# atWork_Remote.net
KiCad netlist of a schematic drawn in Altium Designer
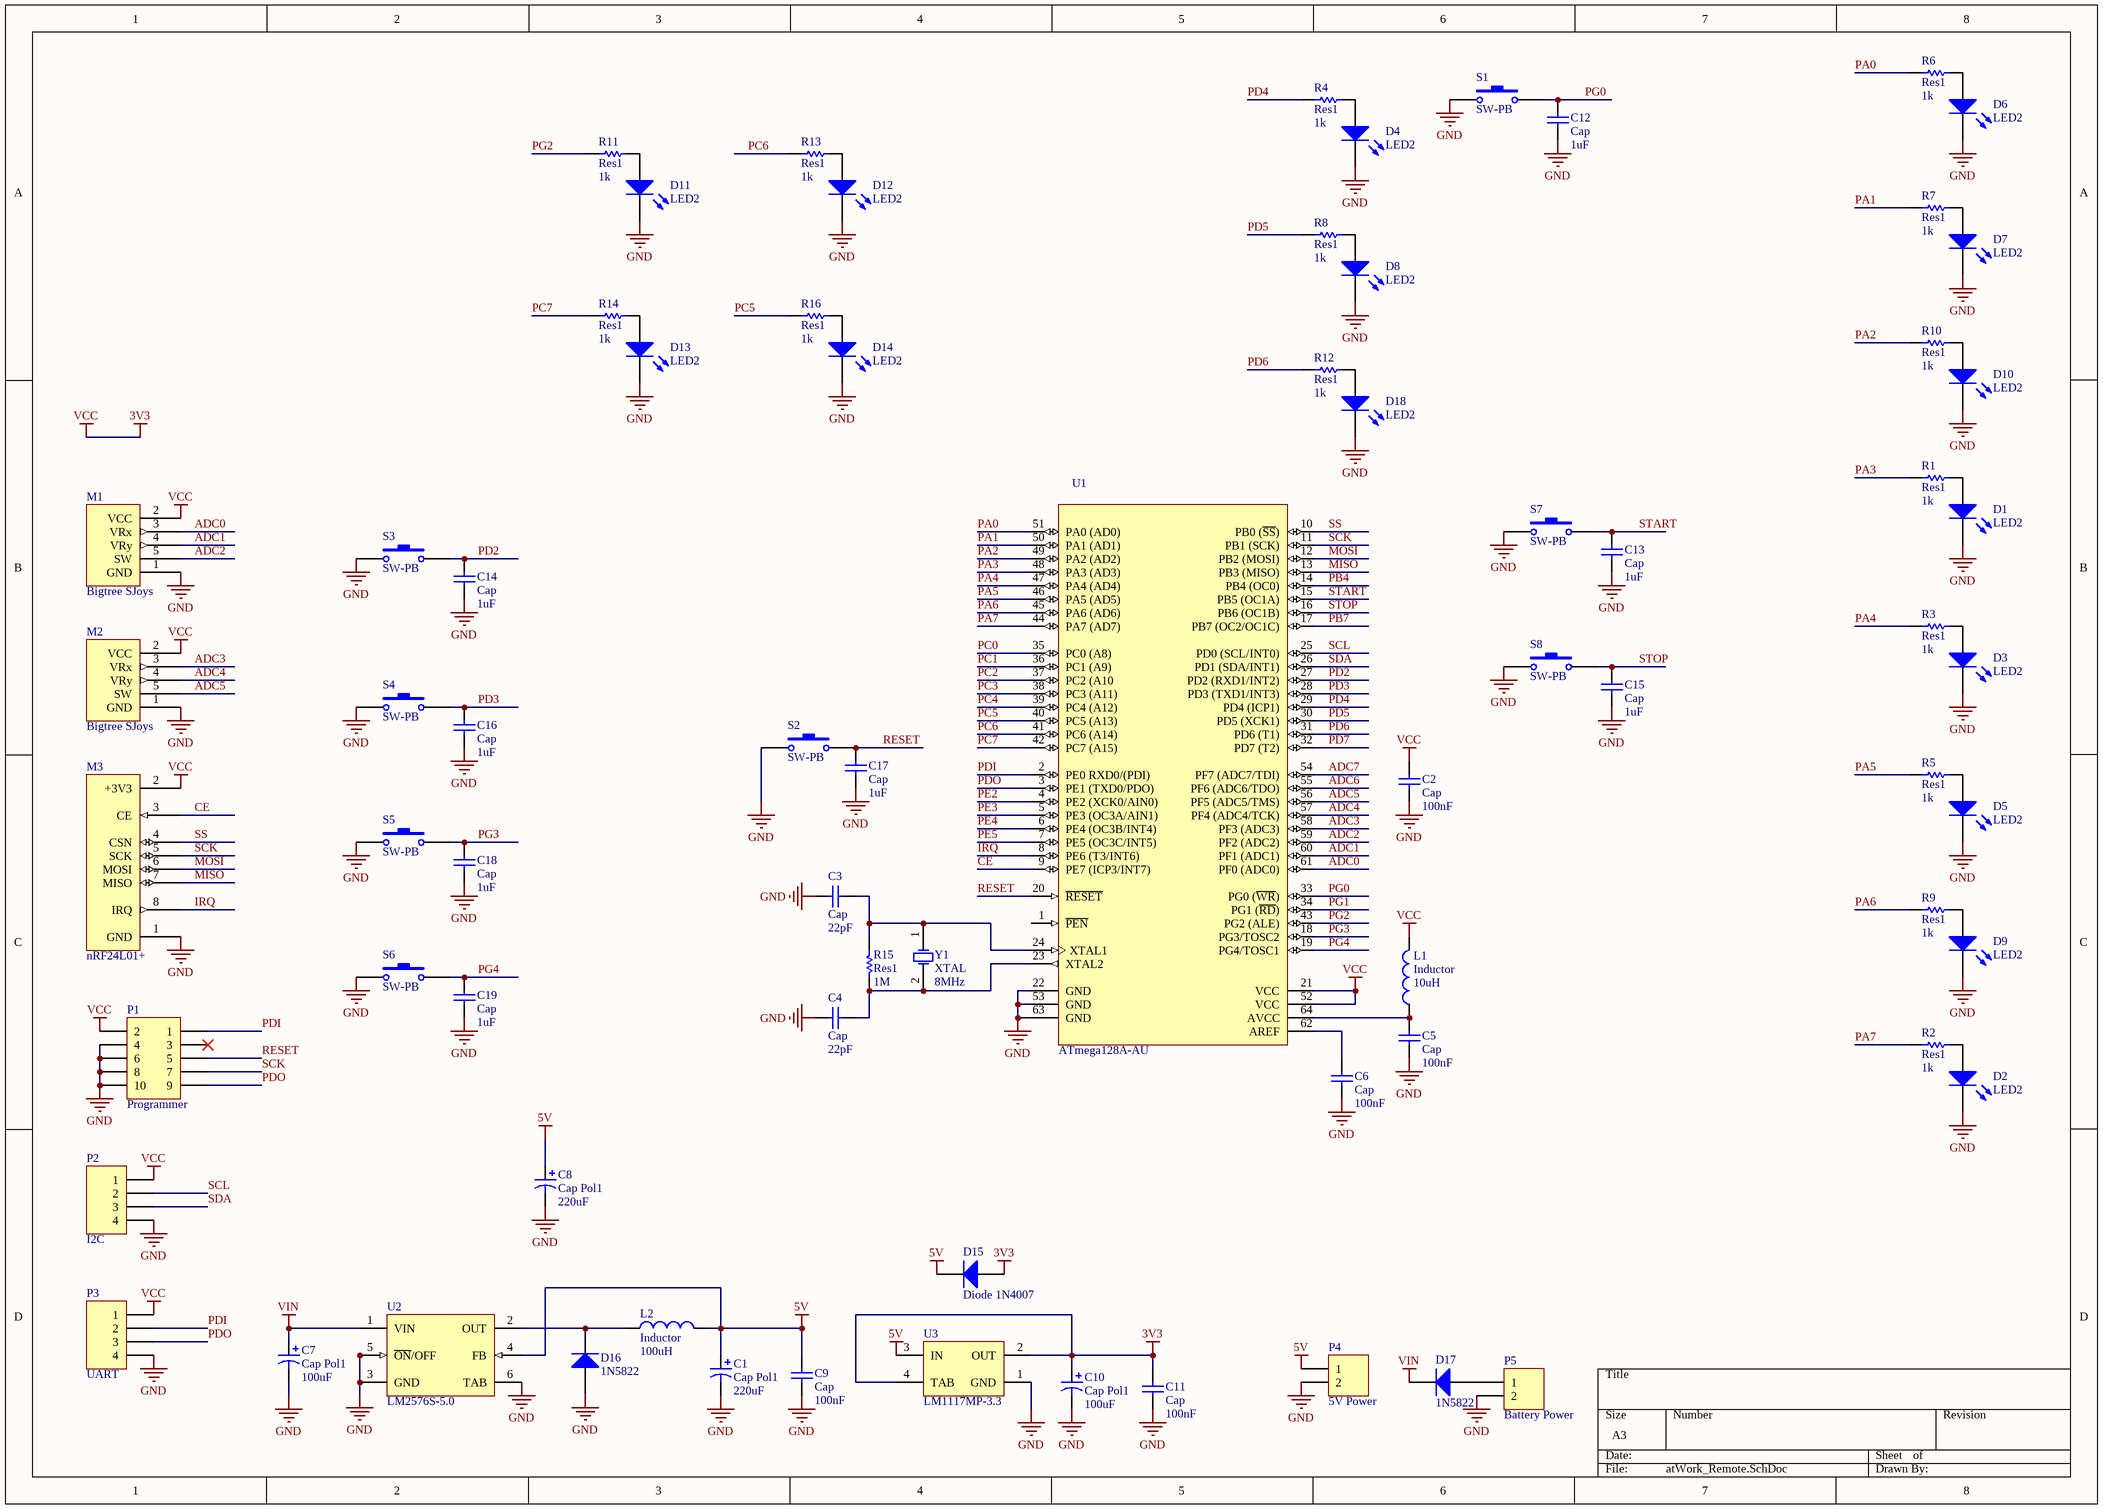
[diagram p0: atWork_Remote.SchDoc]

(export (version "E")
  (design (tool "Eeschema 10.0.6"))
  (components
    (comp (ref "C1")
      (value "Cap Pol1")
      (footprint "CAP-SMD2")
      (description "Polarized Capacitor (Radial)")
      (fields (field (name "ALTIUM_VALUE") "220uF") (field (name "PUBLISHER") "Altium Limited"))
      (libsource (lib "Miscellaneous Devices") (part "Cap Pol1"))
    )
    (comp (ref "C2")
      (value "Cap")
      (footprint "C1206")
      (description "Capacitor")
      (fields (field (name "ALTIUM_VALUE") "100nF") (field (name "PUBLISHER") "Altium Limited"))
      (libsource (lib "Miscellaneous Devices") (part "Cap"))
    )
    (comp (ref "C3")
      (value "Cap")
      (footprint "C1206")
      (description "Capacitor")
      (fields (field (name "ALTIUM_VALUE") "22pF") (field (name "PUBLISHER") "Altium Limited"))
      (libsource (lib "Miscellaneous Devices") (part "Cap"))
    )
    (comp (ref "C4")
      (value "Cap")
      (footprint "C1206")
      (description "Capacitor")
      (fields (field (name "ALTIUM_VALUE") "22pF") (field (name "PUBLISHER") "Altium Limited"))
      (libsource (lib "Miscellaneous Devices") (part "Cap"))
    )
    (comp (ref "C5")
      (value "Cap")
      (footprint "C1206")
      (description "Capacitor")
      (fields (field (name "ALTIUM_VALUE") "100nF") (field (name "PUBLISHER") "Altium Limited"))
      (libsource (lib "Miscellaneous Devices") (part "Cap"))
    )
    (comp (ref "C6")
      (value "Cap")
      (footprint "C1206")
      (description "Capacitor")
      (fields (field (name "ALTIUM_VALUE") "100nF") (field (name "PUBLISHER") "Altium Limited"))
      (libsource (lib "Miscellaneous Devices") (part "Cap"))
    )
    (comp (ref "C7")
      (value "Cap Pol1")
      (footprint "CAP-SMD1")
      (description "Polarized Capacitor (Radial)")
      (fields (field (name "ALTIUM_VALUE") "100uF") (field (name "PUBLISHER") "Altium Limited"))
      (libsource (lib "Miscellaneous Devices") (part "Cap Pol1"))
    )
    (comp (ref "C8")
      (value "Cap Pol1")
      (footprint "CAP-SMD2")
      (description "Polarized Capacitor (Radial)")
      (fields (field (name "ALTIUM_VALUE") "220uF") (field (name "PUBLISHER") "Altium Limited"))
      (libsource (lib "Miscellaneous Devices") (part "Cap Pol1"))
    )
    (comp (ref "C9")
      (value "Cap")
      (footprint "C1206")
      (description "Capacitor")
      (fields (field (name "ALTIUM_VALUE") "100nF") (field (name "PUBLISHER") "Altium Limited"))
      (libsource (lib "Miscellaneous Devices") (part "Cap"))
    )
    (comp (ref "C10")
      (value "Cap Pol1")
      (footprint "CAP-SMD1")
      (description "Polarized Capacitor (Radial)")
      (fields (field (name "ALTIUM_VALUE") "100uF") (field (name "PUBLISHER") "Altium Limited"))
      (libsource (lib "Miscellaneous Devices") (part "Cap Pol1"))
    )
    (comp (ref "C11")
      (value "Cap")
      (footprint "C1206")
      (description "Capacitor")
      (fields (field (name "ALTIUM_VALUE") "100nF") (field (name "PUBLISHER") "Altium Limited"))
      (libsource (lib "Miscellaneous Devices") (part "Cap"))
    )
    (comp (ref "C12")
      (value "Cap")
      (footprint "C1206")
      (description "Capacitor")
      (fields (field (name "ALTIUM_VALUE") "1uF") (field (name "PUBLISHER") "Altium Limited"))
      (libsource (lib "Miscellaneous Devices") (part "Cap"))
    )
    (comp (ref "C13")
      (value "Cap")
      (footprint "C1206")
      (description "Capacitor")
      (fields (field (name "ALTIUM_VALUE") "1uF") (field (name "PUBLISHER") "Altium Limited"))
      (libsource (lib "Miscellaneous Devices") (part "Cap"))
    )
    (comp (ref "C14")
      (value "Cap")
      (footprint "C1206")
      (description "Capacitor")
      (fields (field (name "ALTIUM_VALUE") "1uF") (field (name "PUBLISHER") "Altium Limited"))
      (libsource (lib "Miscellaneous Devices") (part "Cap"))
    )
    (comp (ref "C15")
      (value "Cap")
      (footprint "C1206")
      (description "Capacitor")
      (fields (field (name "ALTIUM_VALUE") "1uF") (field (name "PUBLISHER") "Altium Limited"))
      (libsource (lib "Miscellaneous Devices") (part "Cap"))
    )
    (comp (ref "C16")
      (value "Cap")
      (footprint "C1206")
      (description "Capacitor")
      (fields (field (name "ALTIUM_VALUE") "1uF") (field (name "PUBLISHER") "Altium Limited"))
      (libsource (lib "Miscellaneous Devices") (part "Cap"))
    )
    (comp (ref "C17")
      (value "Cap")
      (footprint "C1206")
      (description "Capacitor")
      (fields (field (name "ALTIUM_VALUE") "1uF") (field (name "PUBLISHER") "Altium Limited"))
      (libsource (lib "Miscellaneous Devices") (part "Cap"))
    )
    (comp (ref "C18")
      (value "Cap")
      (footprint "C1206")
      (description "Capacitor")
      (fields (field (name "ALTIUM_VALUE") "1uF") (field (name "PUBLISHER") "Altium Limited"))
      (libsource (lib "Miscellaneous Devices") (part "Cap"))
    )
    (comp (ref "C19")
      (value "Cap")
      (footprint "C1206")
      (description "Capacitor")
      (fields (field (name "ALTIUM_VALUE") "1uF") (field (name "PUBLISHER") "Altium Limited"))
      (libsource (lib "Miscellaneous Devices") (part "Cap"))
    )
    (comp (ref "D1")
      (value "LED2")
      (footprint "3.2X1.6X1.1")
      (description "Typical RED, GREEN, YELLOW, AMBER GaAs LED")
      (fields (field (name "PUBLISHER") "Altium Limited"))
      (libsource (lib "Miscellaneous Devices") (part "LED2"))
    )
    (comp (ref "D2")
      (value "LED2")
      (footprint "3.2X1.6X1.1")
      (description "Typical RED, GREEN, YELLOW, AMBER GaAs LED")
      (fields (field (name "PUBLISHER") "Altium Limited"))
      (libsource (lib "Miscellaneous Devices") (part "LED2"))
    )
    (comp (ref "D3")
      (value "LED2")
      (footprint "3.2X1.6X1.1")
      (description "Typical RED, GREEN, YELLOW, AMBER GaAs LED")
      (fields (field (name "PUBLISHER") "Altium Limited"))
      (libsource (lib "Miscellaneous Devices") (part "LED2"))
    )
    (comp (ref "D4")
      (value "LED2")
      (footprint "3.2X1.6X1.1")
      (description "Typical RED, GREEN, YELLOW, AMBER GaAs LED")
      (fields (field (name "PUBLISHER") "Altium Limited"))
      (libsource (lib "Miscellaneous Devices") (part "LED2"))
    )
    (comp (ref "D5")
      (value "LED2")
      (footprint "3.2X1.6X1.1")
      (description "Typical RED, GREEN, YELLOW, AMBER GaAs LED")
      (fields (field (name "PUBLISHER") "Altium Limited"))
      (libsource (lib "Miscellaneous Devices") (part "LED2"))
    )
    (comp (ref "D6")
      (value "LED2")
      (footprint "3.2X1.6X1.1")
      (description "Typical RED, GREEN, YELLOW, AMBER GaAs LED")
      (fields (field (name "PUBLISHER") "Altium Limited"))
      (libsource (lib "Miscellaneous Devices") (part "LED2"))
    )
    (comp (ref "D7")
      (value "LED2")
      (footprint "3.2X1.6X1.1")
      (description "Typical RED, GREEN, YELLOW, AMBER GaAs LED")
      (fields (field (name "PUBLISHER") "Altium Limited"))
      (libsource (lib "Miscellaneous Devices") (part "LED2"))
    )
    (comp (ref "D8")
      (value "LED2")
      (footprint "3.2X1.6X1.1")
      (description "Typical RED, GREEN, YELLOW, AMBER GaAs LED")
      (fields (field (name "PUBLISHER") "Altium Limited"))
      (libsource (lib "Miscellaneous Devices") (part "LED2"))
    )
    (comp (ref "D9")
      (value "LED2")
      (footprint "3.2X1.6X1.1")
      (description "Typical RED, GREEN, YELLOW, AMBER GaAs LED")
      (fields (field (name "PUBLISHER") "Altium Limited"))
      (libsource (lib "Miscellaneous Devices") (part "LED2"))
    )
    (comp (ref "D10")
      (value "LED2")
      (footprint "3.2X1.6X1.1")
      (description "Typical RED, GREEN, YELLOW, AMBER GaAs LED")
      (fields (field (name "PUBLISHER") "Altium Limited"))
      (libsource (lib "Miscellaneous Devices") (part "LED2"))
    )
    (comp (ref "D11")
      (value "LED2")
      (footprint "3.2X1.6X1.1")
      (description "Typical RED, GREEN, YELLOW, AMBER GaAs LED")
      (fields (field (name "PUBLISHER") "Altium Limited"))
      (libsource (lib "Miscellaneous Devices") (part "LED2"))
    )
    (comp (ref "D12")
      (value "LED2")
      (footprint "3.2X1.6X1.1")
      (description "Typical RED, GREEN, YELLOW, AMBER GaAs LED")
      (fields (field (name "PUBLISHER") "Altium Limited"))
      (libsource (lib "Miscellaneous Devices") (part "LED2"))
    )
    (comp (ref "D13")
      (value "LED2")
      (footprint "3.2X1.6X1.1")
      (description "Typical RED, GREEN, YELLOW, AMBER GaAs LED")
      (fields (field (name "PUBLISHER") "Altium Limited"))
      (libsource (lib "Miscellaneous Devices") (part "LED2"))
    )
    (comp (ref "D14")
      (value "LED2")
      (footprint "3.2X1.6X1.1")
      (description "Typical RED, GREEN, YELLOW, AMBER GaAs LED")
      (fields (field (name "PUBLISHER") "Altium Limited"))
      (libsource (lib "Miscellaneous Devices") (part "LED2"))
    )
    (comp (ref "D15")
      (value "Diode 1N4007")
      (footprint "DIODE-SMD")
      (description "1 Amp General Purpose Rectifier")
      (fields (field (name "PUBLISHER") "Altium Limited"))
      (libsource (lib "Miscellaneous Devices") (part "Diode 1N4007"))
    )
    (comp (ref "D16")
      (value "1N5822")
      (footprint "DIODE-SMD")
      (description "Default Diode")
      (fields (field (name "PUBLISHER") "Altium Limited"))
      (libsource (lib "Miscellaneous Devices") (part "Diode"))
    )
    (comp (ref "D17")
      (value "1N5822")
      (footprint "DIODE-SMD")
      (description "Default Diode")
      (fields (field (name "PUBLISHER") "Altium Limited"))
      (libsource (lib "Miscellaneous Devices") (part "Diode"))
    )
    (comp (ref "D18")
      (value "LED2")
      (footprint "3.2X1.6X1.1")
      (description "Typical RED, GREEN, YELLOW, AMBER GaAs LED")
      (fields (field (name "PUBLISHER") "Altium Limited"))
      (libsource (lib "Miscellaneous Devices") (part "LED2"))
    )
    (comp (ref "L1")
      (value "Inductor")
      (footprint "C1206")
      (fields (field (name "ALTIUM_VALUE") "10uH") (field (name "PUBLISHER") "Altium Limited"))
      (libsource (lib "Miscellaneous Devices") (part "Inductor"))
    )
    (comp (ref "L2")
      (value "Inductor")
      (footprint "C1206")
      (fields (field (name "ALTIUM_VALUE") "100uH") (field (name "PUBLISHER") "Altium Limited"))
      (libsource (lib "Miscellaneous Devices") (part "Inductor"))
    )
    (comp (ref "M1")
      (value "Bigtree SJoys")
      (footprint "BIGTREE_SJOYS")
      (description "Dual-Axis Joystick with Button")
      (fields (field (name "DESIGNER") "Meysam Parvizi") (field (name "EMAIL") "meysam.parvizi.ir@gmail.com"))
      (libsource (lib "mp") (part "Bigtree SJoys"))
    )
    (comp (ref "M2")
      (value "Bigtree SJoys")
      (footprint "BIGTREE_SJOYS")
      (description "Dual-Axis Joystick with Button")
      (fields (field (name "DESIGNER") "Meysam Parvizi") (field (name "EMAIL") "meysam.parvizi.ir@gmail.com"))
      (libsource (lib "mp") (part "Bigtree SJoys"))
    )
    (comp (ref "M3")
      (value "nRF24L01+")
      (footprint "NRF24L01+")
      (description "nRF24L01 Single Chip 2.4GHz Tranceiver, +PA +LNA Ver5.1")
      (fields (field (name "DESIGNER") "Meysam Parvizi") (field (name "EMAIL") "meysam.parvizi.ir@gmail.com"))
      (libsource (lib "mp") (part "nRF24L01+"))
    )
    (comp (ref "P1")
      (value "Programmer")
      (footprint "BOX2X5_RIGHT")
      (description "Box, 5-Pin, Dual row")
      (fields (field (name "DESIGNER") "Meysam Parvizi") (field (name "EMAIL") "meysam.parvizi.ir@gmail.com"))
      (libsource (lib "mp") (part "Box 5X2"))
    )
    (comp (ref "P2")
      (value "I2C")
      (footprint "XH4PIN")
      (description "Header, 4-Pin")
      (fields (field (name "PUBLISHER") "Altium Limited"))
      (libsource (lib "Miscellaneous Connectors") (part "Header 4"))
    )
    (comp (ref "P3")
      (value "UART")
      (footprint "XH4PIN")
      (description "Header, 4-Pin")
      (fields (field (name "PUBLISHER") "Altium Limited"))
      (libsource (lib "Miscellaneous Connectors") (part "Header 4"))
    )
    (comp (ref "P4")
      (value "5V Power")
      (footprint "XH2PIN")
      (description "Header, 2-Pin")
      (fields (field (name "PUBLISHER") "Altium Limited"))
      (libsource (lib "Miscellaneous Connectors") (part "Header 2"))
    )
    (comp (ref "P5")
      (value "Battery Power")
      (footprint "XH2PIN")
      (description "Header, 2-Pin")
      (fields (field (name "PUBLISHER") "Altium Limited"))
      (libsource (lib "Miscellaneous Connectors") (part "Header 2"))
    )
    (comp (ref "R1")
      (value "Res1")
      (footprint "C1206")
      (description "Resistor")
      (fields (field (name "ALTIUM_VALUE") "1k") (field (name "PUBLISHER") "Altium Limited"))
      (libsource (lib "Miscellaneous Devices") (part "Res1"))
    )
    (comp (ref "R2")
      (value "Res1")
      (footprint "C1206")
      (description "Resistor")
      (fields (field (name "ALTIUM_VALUE") "1k") (field (name "PUBLISHER") "Altium Limited"))
      (libsource (lib "Miscellaneous Devices") (part "Res1"))
    )
    (comp (ref "R3")
      (value "Res1")
      (footprint "C1206")
      (description "Resistor")
      (fields (field (name "ALTIUM_VALUE") "1k") (field (name "PUBLISHER") "Altium Limited"))
      (libsource (lib "Miscellaneous Devices") (part "Res1"))
    )
    (comp (ref "R4")
      (value "Res1")
      (footprint "C1206")
      (description "Resistor")
      (fields (field (name "ALTIUM_VALUE") "1k") (field (name "PUBLISHER") "Altium Limited"))
      (libsource (lib "Miscellaneous Devices") (part "Res1"))
    )
    (comp (ref "R5")
      (value "Res1")
      (footprint "C1206")
      (description "Resistor")
      (fields (field (name "ALTIUM_VALUE") "1k") (field (name "PUBLISHER") "Altium Limited"))
      (libsource (lib "Miscellaneous Devices") (part "Res1"))
    )
    (comp (ref "R6")
      (value "Res1")
      (footprint "C1206")
      (description "Resistor")
      (fields (field (name "ALTIUM_VALUE") "1k") (field (name "PUBLISHER") "Altium Limited"))
      (libsource (lib "Miscellaneous Devices") (part "Res1"))
    )
    (comp (ref "R7")
      (value "Res1")
      (footprint "C1206")
      (description "Resistor")
      (fields (field (name "ALTIUM_VALUE") "1k") (field (name "PUBLISHER") "Altium Limited"))
      (libsource (lib "Miscellaneous Devices") (part "Res1"))
    )
    (comp (ref "R8")
      (value "Res1")
      (footprint "C1206")
      (description "Resistor")
      (fields (field (name "ALTIUM_VALUE") "1k") (field (name "PUBLISHER") "Altium Limited"))
      (libsource (lib "Miscellaneous Devices") (part "Res1"))
    )
    (comp (ref "R9")
      (value "Res1")
      (footprint "C1206")
      (description "Resistor")
      (fields (field (name "ALTIUM_VALUE") "1k") (field (name "PUBLISHER") "Altium Limited"))
      (libsource (lib "Miscellaneous Devices") (part "Res1"))
    )
    (comp (ref "R10")
      (value "Res1")
      (footprint "C1206")
      (description "Resistor")
      (fields (field (name "ALTIUM_VALUE") "1k") (field (name "PUBLISHER") "Altium Limited"))
      (libsource (lib "Miscellaneous Devices") (part "Res1"))
    )
    (comp (ref "R11")
      (value "Res1")
      (footprint "C1206")
      (description "Resistor")
      (fields (field (name "ALTIUM_VALUE") "1k") (field (name "PUBLISHER") "Altium Limited"))
      (libsource (lib "Miscellaneous Devices") (part "Res1"))
    )
    (comp (ref "R12")
      (value "Res1")
      (footprint "C1206")
      (description "Resistor")
      (fields (field (name "ALTIUM_VALUE") "1k") (field (name "PUBLISHER") "Altium Limited"))
      (libsource (lib "Miscellaneous Devices") (part "Res1"))
    )
    (comp (ref "R13")
      (value "Res1")
      (footprint "C1206")
      (description "Resistor")
      (fields (field (name "ALTIUM_VALUE") "1k") (field (name "PUBLISHER") "Altium Limited"))
      (libsource (lib "Miscellaneous Devices") (part "Res1"))
    )
    (comp (ref "R14")
      (value "Res1")
      (footprint "C1206")
      (description "Resistor")
      (fields (field (name "ALTIUM_VALUE") "1k") (field (name "PUBLISHER") "Altium Limited"))
      (libsource (lib "Miscellaneous Devices") (part "Res1"))
    )
    (comp (ref "R15")
      (value "Res1")
      (footprint "C1206")
      (description "Resistor")
      (fields (field (name "ALTIUM_VALUE") "1M") (field (name "PUBLISHER") "Altium Limited"))
      (libsource (lib "Miscellaneous Devices") (part "Res1"))
    )
    (comp (ref "R16")
      (value "Res1")
      (footprint "C1206")
      (description "Resistor")
      (fields (field (name "ALTIUM_VALUE") "1k") (field (name "PUBLISHER") "Altium Limited"))
      (libsource (lib "Miscellaneous Devices") (part "Res1"))
    )
    (comp (ref "S1")
      (value "SW-PB")
      (footprint "PUSH1")
      (description "Switch")
      (fields (field (name "PUBLISHER") "Altium Limited"))
      (libsource (lib "mp") (part "SW-PB"))
    )
    (comp (ref "S2")
      (value "SW-PB")
      (footprint "PUSH1")
      (description "Switch")
      (fields (field (name "PUBLISHER") "Altium Limited"))
      (libsource (lib "mp") (part "SW-PB"))
    )
    (comp (ref "S3")
      (value "SW-PB")
      (footprint "PUSH-OMRON")
      (description "Switch")
      (fields (field (name "PUBLISHER") "Altium Limited"))
      (libsource (lib "mp") (part "SW-PB"))
    )
    (comp (ref "S4")
      (value "SW-PB")
      (footprint "PUSH-OMRON")
      (description "Switch")
      (fields (field (name "PUBLISHER") "Altium Limited"))
      (libsource (lib "mp") (part "SW-PB"))
    )
    (comp (ref "S5")
      (value "SW-PB")
      (footprint "PUSH-OMRON")
      (description "Switch")
      (fields (field (name "PUBLISHER") "Altium Limited"))
      (libsource (lib "mp") (part "SW-PB"))
    )
    (comp (ref "S6")
      (value "SW-PB")
      (footprint "PUSH-OMRON")
      (description "Switch")
      (fields (field (name "PUBLISHER") "Altium Limited"))
      (libsource (lib "mp") (part "SW-PB"))
    )
    (comp (ref "S7")
      (value "SW-PB")
      (footprint "PUSH1")
      (description "Switch")
      (fields (field (name "PUBLISHER") "Altium Limited"))
      (libsource (lib "mp") (part "SW-PB"))
    )
    (comp (ref "S8")
      (value "SW-PB")
      (footprint "PUSH1")
      (description "Switch")
      (fields (field (name "PUBLISHER") "Altium Limited"))
      (libsource (lib "mp") (part "SW-PB"))
    )
    (comp (ref "U1")
      (value "ATmega128A-AU")
      (footprint "64A_M")
      (fields (field (name "PUBLISHER") "Altium Limited"))
      (libsource (lib "Atmel Microcontroller 8-Bit megaAVR") (part "ATmega128A-AU"))
    )
    (comp (ref "U2")
      (value "LM2576S-5.0")
      (footprint "TS5B_M")
      (description "SIMPLE SWITCHER® 3A Step-Down Voltage Regulator, 5-pin TO-263")
      (fields
        (field (name "MANUFACTURER") "National Semiconductor")
        (field (name "PUBLISHER") "Altium Limited")
      )
      (libsource (lib "NSC Switcher") (part "LM2576S-5.0"))
    )
    (comp (ref "U3")
      (value "LM1117MP-3.3")
      (footprint "MP04A_M")
      (description "800mA Low-Dropout Linear Regulator, 4-pin SOT-223")
      (fields
        (field (name "MANUFACTURER") "National Semiconductor")
        (field (name "PUBLISHER") "Altium Limited")
      )
      (libsource (lib "NSC LDO") (part "LM1117MP-3.3"))
    )
    (comp (ref "Y1")
      (value "XTAL")
      (footprint "XTAL-SMD")
      (description "Crystal Oscillator")
      (fields
        (field (name "ALTIUM_VALUE") "8MHz")
        (field (name "DESIGNER") "Meysam Parvizi")
        (field (name "EMAIL") "meysam.parvizi.ir@gmail.com")
      )
      (libsource (lib "mp") (part "XTAL"))
    )
  )
  (nets
    (net (code "1") (name "/ADC0") (class "Default")
      (node (ref "M1") (pin "3") (pinfunction "VRx_3") (pintype "output"))
      (node (ref "U1") (pin "61") (pinfunction "PF0_(ADC0)_61") (pintype "bidirectional"))
    )
    (net (code "2") (name "/ADC1") (class "Default")
      (node (ref "M1") (pin "4") (pinfunction "VRy_4") (pintype "output"))
      (node (ref "U1") (pin "60") (pinfunction "PF1_(ADC1)_60") (pintype "bidirectional"))
    )
    (net (code "3") (name "/ADC2") (class "Default")
      (node (ref "M1") (pin "5") (pinfunction "SW_5") (pintype "passive"))
      (node (ref "U1") (pin "59") (pinfunction "PF2_(ADC2)_59") (pintype "bidirectional"))
    )
    (net (code "4") (name "/ADC3") (class "Default")
      (node (ref "M2") (pin "3") (pinfunction "VRx_3") (pintype "output"))
      (node (ref "U1") (pin "58") (pinfunction "PF3_(ADC3)_58") (pintype "bidirectional"))
    )
    (net (code "5") (name "/ADC4") (class "Default")
      (node (ref "M2") (pin "4") (pinfunction "VRy_4") (pintype "output"))
      (node (ref "U1") (pin "57") (pinfunction "PF4_(ADC4/TCK)_57") (pintype "bidirectional"))
    )
    (net (code "6") (name "/ADC5") (class "Default")
      (node (ref "M2") (pin "5") (pinfunction "SW_5") (pintype "passive"))
      (node (ref "U1") (pin "56") (pinfunction "PF5_(ADC5/TMS)_56") (pintype "bidirectional"))
    )
    (net (code "7") (name "/ADC6") (class "Default")
      (node (ref "U1") (pin "55") (pinfunction "PF6_(ADC6/TDO)_55") (pintype "bidirectional"))
    )
    (net (code "8") (name "/ADC7") (class "Default")
      (node (ref "U1") (pin "54") (pinfunction "PF7_(ADC7/TDI)_54") (pintype "bidirectional"))
    )
    (net (code "9") (name "/CE") (class "Default")
      (node (ref "M3") (pin "3") (pinfunction "CE_3") (pintype "input"))
      (node (ref "U1") (pin "9") (pinfunction "PE7_(ICP3/INT7)_9") (pintype "bidirectional"))
    )
    (net (code "10") (name "/IRQ") (class "Default")
      (node (ref "M3") (pin "8") (pinfunction "IRQ_8") (pintype "output"))
      (node (ref "U1") (pin "8") (pinfunction "PE6_(T3/INT6)_8") (pintype "bidirectional"))
    )
    (net (code "11") (name "/MISO") (class "Default")
      (node (ref "M3") (pin "7") (pinfunction "MISO_7") (pintype "bidirectional"))
      (node (ref "U1") (pin "13") (pinfunction "PB3_(MISO)_13") (pintype "bidirectional"))
    )
    (net (code "12") (name "/MOSI") (class "Default")
      (node (ref "M3") (pin "6") (pinfunction "MOSI_6") (pintype "bidirectional"))
      (node (ref "U1") (pin "12") (pinfunction "PB2_(MOSI)_12") (pintype "bidirectional"))
    )
    (net (code "13") (name "/PA0") (class "Default")
      (node (ref "R6") (pin "2") (pinfunction "2_2") (pintype "passive"))
      (node (ref "U1") (pin "51") (pinfunction "PA0_(AD0)_51") (pintype "bidirectional"))
    )
    (net (code "14") (name "/PA1") (class "Default")
      (node (ref "R7") (pin "2") (pinfunction "2_2") (pintype "passive"))
      (node (ref "U1") (pin "50") (pinfunction "PA1_(AD1)_50") (pintype "bidirectional"))
    )
    (net (code "15") (name "/PA2") (class "Default")
      (node (ref "R10") (pin "2") (pinfunction "2_2") (pintype "passive"))
      (node (ref "U1") (pin "49") (pinfunction "PA2_(AD2)_49") (pintype "bidirectional"))
    )
    (net (code "16") (name "/PA3") (class "Default")
      (node (ref "R1") (pin "2") (pinfunction "2_2") (pintype "passive"))
      (node (ref "U1") (pin "48") (pinfunction "PA3_(AD3)_48") (pintype "bidirectional"))
    )
    (net (code "17") (name "/PA4") (class "Default")
      (node (ref "R3") (pin "2") (pinfunction "2_2") (pintype "passive"))
      (node (ref "U1") (pin "47") (pinfunction "PA4_(AD4)_47") (pintype "bidirectional"))
    )
    (net (code "18") (name "/PA5") (class "Default")
      (node (ref "R5") (pin "2") (pinfunction "2_2") (pintype "passive"))
      (node (ref "U1") (pin "46") (pinfunction "PA5_(AD5)_46") (pintype "bidirectional"))
    )
    (net (code "19") (name "/PA6") (class "Default")
      (node (ref "R9") (pin "2") (pinfunction "2_2") (pintype "passive"))
      (node (ref "U1") (pin "45") (pinfunction "PA6_(AD6)_45") (pintype "bidirectional"))
    )
    (net (code "20") (name "/PA7") (class "Default")
      (node (ref "R2") (pin "2") (pinfunction "2_2") (pintype "passive"))
      (node (ref "U1") (pin "44") (pinfunction "PA7_(AD7)_44") (pintype "bidirectional"))
    )
    (net (code "21") (name "/PB4") (class "Default")
      (node (ref "U1") (pin "14") (pinfunction "PB4_(OC0)_14") (pintype "bidirectional"))
    )
    (net (code "22") (name "/PB7") (class "Default")
      (node (ref "U1") (pin "17") (pinfunction "PB7_(OC2/OC1C)_17") (pintype "bidirectional"))
    )
    (net (code "23") (name "/PC0") (class "Default")
      (node (ref "U1") (pin "35") (pinfunction "PC0_(A8)_35") (pintype "bidirectional"))
    )
    (net (code "24") (name "/PC1") (class "Default")
      (node (ref "U1") (pin "36") (pinfunction "PC1_(A9)_36") (pintype "bidirectional"))
    )
    (net (code "25") (name "/PC2") (class "Default")
      (node (ref "U1") (pin "37") (pinfunction "PC2_(A10_37") (pintype "bidirectional"))
    )
    (net (code "26") (name "/PC3") (class "Default")
      (node (ref "U1") (pin "38") (pinfunction "PC3_(A11)_38") (pintype "bidirectional"))
    )
    (net (code "27") (name "/PC4") (class "Default")
      (node (ref "U1") (pin "39") (pinfunction "PC4_(A12)_39") (pintype "bidirectional"))
    )
    (net (code "28") (name "/PC5") (class "Default")
      (node (ref "R16") (pin "2") (pinfunction "2_2") (pintype "passive"))
      (node (ref "U1") (pin "40") (pinfunction "PC5_(A13)_40") (pintype "bidirectional"))
    )
    (net (code "29") (name "/PC6") (class "Default")
      (node (ref "R13") (pin "2") (pinfunction "2_2") (pintype "passive"))
      (node (ref "U1") (pin "41") (pinfunction "PC6_(A14)_41") (pintype "bidirectional"))
    )
    (net (code "30") (name "/PC7") (class "Default")
      (node (ref "R14") (pin "2") (pinfunction "2_2") (pintype "passive"))
      (node (ref "U1") (pin "42") (pinfunction "PC7_(A15)_42") (pintype "bidirectional"))
    )
    (net (code "31") (name "/PD2") (class "Default")
      (node (ref "C14") (pin "1") (pinfunction "1_1") (pintype "passive"))
      (node (ref "S3") (pin "2") (pinfunction "2_2") (pintype "passive"))
      (node (ref "U1") (pin "27") (pinfunction "PD2_(RXD1/INT2)_27") (pintype "bidirectional"))
    )
    (net (code "32") (name "/PD3") (class "Default")
      (node (ref "C16") (pin "1") (pinfunction "1_1") (pintype "passive"))
      (node (ref "S4") (pin "2") (pinfunction "2_2") (pintype "passive"))
      (node (ref "U1") (pin "28") (pinfunction "PD3_(TXD1/INT3)_28") (pintype "bidirectional"))
    )
    (net (code "33") (name "/PD4") (class "Default")
      (node (ref "R4") (pin "2") (pinfunction "2_2") (pintype "passive"))
      (node (ref "U1") (pin "29") (pinfunction "PD4_(ICP1)_29") (pintype "bidirectional"))
    )
    (net (code "34") (name "/PD5") (class "Default")
      (node (ref "R8") (pin "2") (pinfunction "2_2") (pintype "passive"))
      (node (ref "U1") (pin "30") (pinfunction "PD5_(XCK1)_30") (pintype "bidirectional"))
    )
    (net (code "35") (name "/PD6") (class "Default")
      (node (ref "R12") (pin "2") (pinfunction "2_2") (pintype "passive"))
      (node (ref "U1") (pin "31") (pinfunction "PD6_(T1)_31") (pintype "bidirectional"))
    )
    (net (code "36") (name "/PD7") (class "Default")
      (node (ref "U1") (pin "32") (pinfunction "PD7_(T2)_32") (pintype "bidirectional"))
    )
    (net (code "37") (name "/PDI") (class "Default")
      (node (ref "P1") (pin "1") (pinfunction "1_1") (pintype "passive"))
      (node (ref "P3") (pin "2") (pinfunction "2_2") (pintype "passive"))
      (node (ref "U1") (pin "2") (pinfunction "PE0_RXD0/(PDI)_2") (pintype "bidirectional"))
    )
    (net (code "38") (name "/PDO") (class "Default")
      (node (ref "P1") (pin "9") (pinfunction "9_9") (pintype "passive"))
      (node (ref "P3") (pin "3") (pinfunction "3_3") (pintype "passive"))
      (node (ref "U1") (pin "3") (pinfunction "PE1_(TXD0/PDO)_3") (pintype "bidirectional"))
    )
    (net (code "39") (name "/PE2") (class "Default")
      (node (ref "U1") (pin "4") (pinfunction "PE2_(XCK0/AIN0)_4") (pintype "bidirectional"))
    )
    (net (code "40") (name "/PE3") (class "Default")
      (node (ref "U1") (pin "5") (pinfunction "PE3_(OC3A/AIN1)_5") (pintype "bidirectional"))
    )
    (net (code "41") (name "/PE4") (class "Default")
      (node (ref "U1") (pin "6") (pinfunction "PE4_(OC3B/INT4)_6") (pintype "bidirectional"))
    )
    (net (code "42") (name "/PE5") (class "Default")
      (node (ref "U1") (pin "7") (pinfunction "PE5_(OC3C/INT5)_7") (pintype "bidirectional"))
    )
    (net (code "43") (name "/PG0") (class "Default")
      (node (ref "C12") (pin "1") (pinfunction "1_1") (pintype "passive"))
      (node (ref "S1") (pin "2") (pinfunction "2_2") (pintype "passive"))
      (node (ref "U1") (pin "33") (pinfunction "PG0_(~{WR})_33") (pintype "bidirectional"))
    )
    (net (code "44") (name "/PG1") (class "Default")
      (node (ref "U1") (pin "34") (pinfunction "PG1_(~{RD})_34") (pintype "bidirectional"))
    )
    (net (code "45") (name "/PG2") (class "Default")
      (node (ref "R11") (pin "2") (pinfunction "2_2") (pintype "passive"))
      (node (ref "U1") (pin "43") (pinfunction "PG2_(ALE)_43") (pintype "bidirectional"))
    )
    (net (code "46") (name "/PG3") (class "Default")
      (node (ref "C18") (pin "1") (pinfunction "1_1") (pintype "passive"))
      (node (ref "S5") (pin "2") (pinfunction "2_2") (pintype "passive"))
      (node (ref "U1") (pin "18") (pinfunction "PG3/TOSC2_18") (pintype "bidirectional"))
    )
    (net (code "47") (name "/PG4") (class "Default")
      (node (ref "C19") (pin "1") (pinfunction "1_1") (pintype "passive"))
      (node (ref "S6") (pin "2") (pinfunction "2_2") (pintype "passive"))
      (node (ref "U1") (pin "19") (pinfunction "PG4/TOSC1_19") (pintype "bidirectional"))
    )
    (net (code "48") (name "/RESET") (class "Default")
      (node (ref "C17") (pin "1") (pinfunction "1_1") (pintype "passive"))
      (node (ref "P1") (pin "5") (pinfunction "5_5") (pintype "passive"))
      (node (ref "S2") (pin "2") (pinfunction "2_2") (pintype "passive"))
      (node (ref "U1") (pin "20") (pinfunction "~{RESET}_20") (pintype "input"))
    )
    (net (code "49") (name "/SCK") (class "Default")
      (node (ref "M3") (pin "5") (pinfunction "SCK_5") (pintype "bidirectional"))
      (node (ref "P1") (pin "7") (pinfunction "7_7") (pintype "passive"))
      (node (ref "U1") (pin "11") (pinfunction "PB1_(SCK)_11") (pintype "bidirectional"))
    )
    (net (code "50") (name "/SCL") (class "Default")
      (node (ref "P2") (pin "2") (pinfunction "2_2") (pintype "passive"))
      (node (ref "U1") (pin "25") (pinfunction "PD0_(SCL/INT0)_25") (pintype "bidirectional"))
    )
    (net (code "51") (name "/SDA") (class "Default")
      (node (ref "P2") (pin "3") (pinfunction "3_3") (pintype "passive"))
      (node (ref "U1") (pin "26") (pinfunction "PD1_(SDA/INT1)_26") (pintype "bidirectional"))
    )
    (net (code "52") (name "/SS") (class "Default")
      (node (ref "M3") (pin "4") (pinfunction "CSN_4") (pintype "bidirectional"))
      (node (ref "U1") (pin "10") (pinfunction "PB0_(~{SS})_10") (pintype "bidirectional"))
    )
    (net (code "53") (name "/START") (class "Default")
      (node (ref "C13") (pin "1") (pinfunction "1_1") (pintype "passive"))
      (node (ref "S7") (pin "2") (pinfunction "2_2") (pintype "passive"))
      (node (ref "U1") (pin "15") (pinfunction "PB5_(OC1A)_15") (pintype "bidirectional"))
    )
    (net (code "54") (name "/STOP") (class "Default")
      (node (ref "C15") (pin "1") (pinfunction "1_1") (pintype "passive"))
      (node (ref "S8") (pin "2") (pinfunction "2_2") (pintype "passive"))
      (node (ref "U1") (pin "16") (pinfunction "PB6_(OC1B)_16") (pintype "bidirectional"))
    )
    (net (code "55") (name "3V3") (class "Default")
      (node (ref "C10") (pin "1") (pinfunction "1_1") (pintype "passive"))
      (node (ref "C11") (pin "2") (pinfunction "2_2") (pintype "passive"))
      (node (ref "C2") (pin "2") (pinfunction "2_2") (pintype "passive"))
      (node (ref "D15") (pin "1") (pinfunction "A_1") (pintype "passive"))
      (node (ref "L1") (pin "2") (pinfunction "2_2") (pintype "passive"))
      (node (ref "M1") (pin "2") (pinfunction "VCC_2") (pintype "power_in"))
      (node (ref "M2") (pin "2") (pinfunction "VCC_2") (pintype "power_in"))
      (node (ref "M3") (pin "2") (pinfunction "+3V3_2") (pintype "power_in"))
      (node (ref "P1") (pin "2") (pinfunction "2_2") (pintype "passive"))
      (node (ref "P2") (pin "1") (pinfunction "1_1") (pintype "passive"))
      (node (ref "P3") (pin "1") (pinfunction "1_1") (pintype "passive"))
      (node (ref "U1") (pin "21") (pinfunction "VCC_21") (pintype "power_in"))
      (node (ref "U1") (pin "52") (pinfunction "VCC_52") (pintype "power_in"))
      (node (ref "U3") (pin "2") (pinfunction "OUT_2") (pintype "power_in"))
      (node (ref "U3") (pin "4") (pinfunction "TAB_4") (pintype "power_in"))
    )
    (net (code "56") (name "5V") (class "Default")
      (node (ref "C1") (pin "1") (pinfunction "1_1") (pintype "passive"))
      (node (ref "C8") (pin "1") (pinfunction "1_1") (pintype "passive"))
      (node (ref "C9") (pin "2") (pinfunction "2_2") (pintype "passive"))
      (node (ref "D15") (pin "2") (pinfunction "K_2") (pintype "passive"))
      (node (ref "L2") (pin "2") (pinfunction "2_2") (pintype "passive"))
      (node (ref "P4") (pin "1") (pinfunction "1_1") (pintype "passive"))
      (node (ref "U2") (pin "4") (pinfunction "FB_4") (pintype "input"))
      (node (ref "U3") (pin "3") (pinfunction "IN_3") (pintype "power_in"))
    )
    (net (code "57") (name "GND") (class "Default")
      (node (ref "C1") (pin "2") (pinfunction "2_2") (pintype "passive"))
      (node (ref "C10") (pin "2") (pinfunction "2_2") (pintype "passive"))
      (node (ref "C11") (pin "1") (pinfunction "1_1") (pintype "passive"))
      (node (ref "C12") (pin "2") (pinfunction "2_2") (pintype "passive"))
      (node (ref "C13") (pin "2") (pinfunction "2_2") (pintype "passive"))
      (node (ref "C14") (pin "2") (pinfunction "2_2") (pintype "passive"))
      (node (ref "C15") (pin "2") (pinfunction "2_2") (pintype "passive"))
      (node (ref "C16") (pin "2") (pinfunction "2_2") (pintype "passive"))
      (node (ref "C17") (pin "2") (pinfunction "2_2") (pintype "passive"))
      (node (ref "C18") (pin "2") (pinfunction "2_2") (pintype "passive"))
      (node (ref "C19") (pin "2") (pinfunction "2_2") (pintype "passive"))
      (node (ref "C2") (pin "1") (pinfunction "1_1") (pintype "passive"))
      (node (ref "C3") (pin "1") (pinfunction "1_1") (pintype "passive"))
      (node (ref "C4") (pin "1") (pinfunction "1_1") (pintype "passive"))
      (node (ref "C5") (pin "1") (pinfunction "1_1") (pintype "passive"))
      (node (ref "C6") (pin "1") (pinfunction "1_1") (pintype "passive"))
      (node (ref "C7") (pin "2") (pinfunction "2_2") (pintype "passive"))
      (node (ref "C8") (pin "2") (pinfunction "2_2") (pintype "passive"))
      (node (ref "C9") (pin "1") (pinfunction "1_1") (pintype "passive"))
      (node (ref "D1") (pin "2") (pinfunction "K_2") (pintype "passive"))
      (node (ref "D10") (pin "2") (pinfunction "K_2") (pintype "passive"))
      (node (ref "D11") (pin "2") (pinfunction "K_2") (pintype "passive"))
      (node (ref "D12") (pin "2") (pinfunction "K_2") (pintype "passive"))
      (node (ref "D13") (pin "2") (pinfunction "K_2") (pintype "passive"))
      (node (ref "D14") (pin "2") (pinfunction "K_2") (pintype "passive"))
      (node (ref "D16") (pin "1") (pinfunction "A_1") (pintype "passive"))
      (node (ref "D18") (pin "2") (pinfunction "K_2") (pintype "passive"))
      (node (ref "D2") (pin "2") (pinfunction "K_2") (pintype "passive"))
      (node (ref "D3") (pin "2") (pinfunction "K_2") (pintype "passive"))
      (node (ref "D4") (pin "2") (pinfunction "K_2") (pintype "passive"))
      (node (ref "D5") (pin "2") (pinfunction "K_2") (pintype "passive"))
      (node (ref "D6") (pin "2") (pinfunction "K_2") (pintype "passive"))
      (node (ref "D7") (pin "2") (pinfunction "K_2") (pintype "passive"))
      (node (ref "D8") (pin "2") (pinfunction "K_2") (pintype "passive"))
      (node (ref "D9") (pin "2") (pinfunction "K_2") (pintype "passive"))
      (node (ref "M1") (pin "1") (pinfunction "GND_1") (pintype "power_in"))
      (node (ref "M2") (pin "1") (pinfunction "GND_1") (pintype "power_in"))
      (node (ref "M3") (pin "1") (pinfunction "GND_1") (pintype "power_in"))
      (node (ref "P1") (pin "10") (pinfunction "10_10") (pintype "passive"))
      (node (ref "P1") (pin "4") (pinfunction "4_4") (pintype "passive"))
      (node (ref "P1") (pin "6") (pinfunction "6_6") (pintype "passive"))
      (node (ref "P1") (pin "8") (pinfunction "8_8") (pintype "passive"))
      (node (ref "P2") (pin "4") (pinfunction "4_4") (pintype "passive"))
      (node (ref "P3") (pin "4") (pinfunction "4_4") (pintype "passive"))
      (node (ref "P4") (pin "2") (pinfunction "2_2") (pintype "passive"))
      (node (ref "P5") (pin "2") (pinfunction "2_2") (pintype "passive"))
      (node (ref "S1") (pin "1") (pinfunction "1_1") (pintype "passive"))
      (node (ref "S2") (pin "1") (pinfunction "1_1") (pintype "passive"))
      (node (ref "S3") (pin "1") (pinfunction "1_1") (pintype "passive"))
      (node (ref "S4") (pin "1") (pinfunction "1_1") (pintype "passive"))
      (node (ref "S5") (pin "1") (pinfunction "1_1") (pintype "passive"))
      (node (ref "S6") (pin "1") (pinfunction "1_1") (pintype "passive"))
      (node (ref "S7") (pin "1") (pinfunction "1_1") (pintype "passive"))
      (node (ref "S8") (pin "1") (pinfunction "1_1") (pintype "passive"))
      (node (ref "U1") (pin "22") (pinfunction "GND_22") (pintype "power_in"))
      (node (ref "U1") (pin "53") (pinfunction "GND_53") (pintype "power_in"))
      (node (ref "U1") (pin "63") (pinfunction "GND_63") (pintype "power_in"))
      (node (ref "U2") (pin "3") (pinfunction "GND_3") (pintype "power_in"))
      (node (ref "U2") (pin "5") (pinfunction "~{ON}/OFF_5") (pintype "input"))
      (node (ref "U2") (pin "6") (pinfunction "TAB_6") (pintype "power_in"))
      (node (ref "U3") (pin "1") (pinfunction "GND_1") (pintype "power_in"))
    )
    (net (code "58") (name "Net-(D1-A)") (class "Default")
      (node (ref "D1") (pin "1") (pinfunction "A_1") (pintype "passive"))
      (node (ref "R1") (pin "1") (pinfunction "1_1") (pintype "passive"))
    )
    (net (code "59") (name "Net-(D2-A)") (class "Default")
      (node (ref "D2") (pin "1") (pinfunction "A_1") (pintype "passive"))
      (node (ref "R2") (pin "1") (pinfunction "1_1") (pintype "passive"))
    )
    (net (code "60") (name "Net-(D3-A)") (class "Default")
      (node (ref "D3") (pin "1") (pinfunction "A_1") (pintype "passive"))
      (node (ref "R3") (pin "1") (pinfunction "1_1") (pintype "passive"))
    )
    (net (code "61") (name "Net-(D4-A)") (class "Default")
      (node (ref "D4") (pin "1") (pinfunction "A_1") (pintype "passive"))
      (node (ref "R4") (pin "1") (pinfunction "1_1") (pintype "passive"))
    )
    (net (code "62") (name "Net-(D5-A)") (class "Default")
      (node (ref "D5") (pin "1") (pinfunction "A_1") (pintype "passive"))
      (node (ref "R5") (pin "1") (pinfunction "1_1") (pintype "passive"))
    )
    (net (code "63") (name "Net-(D6-A)") (class "Default")
      (node (ref "D6") (pin "1") (pinfunction "A_1") (pintype "passive"))
      (node (ref "R6") (pin "1") (pinfunction "1_1") (pintype "passive"))
    )
    (net (code "64") (name "Net-(D7-A)") (class "Default")
      (node (ref "D7") (pin "1") (pinfunction "A_1") (pintype "passive"))
      (node (ref "R7") (pin "1") (pinfunction "1_1") (pintype "passive"))
    )
    (net (code "65") (name "Net-(D8-A)") (class "Default")
      (node (ref "D8") (pin "1") (pinfunction "A_1") (pintype "passive"))
      (node (ref "R8") (pin "1") (pinfunction "1_1") (pintype "passive"))
    )
    (net (code "66") (name "Net-(D9-A)") (class "Default")
      (node (ref "D9") (pin "1") (pinfunction "A_1") (pintype "passive"))
      (node (ref "R9") (pin "1") (pinfunction "1_1") (pintype "passive"))
    )
    (net (code "67") (name "Net-(D10-A)") (class "Default")
      (node (ref "D10") (pin "1") (pinfunction "A_1") (pintype "passive"))
      (node (ref "R10") (pin "1") (pinfunction "1_1") (pintype "passive"))
    )
    (net (code "68") (name "Net-(D11-A)") (class "Default")
      (node (ref "D11") (pin "1") (pinfunction "A_1") (pintype "passive"))
      (node (ref "R11") (pin "1") (pinfunction "1_1") (pintype "passive"))
    )
    (net (code "69") (name "Net-(D12-A)") (class "Default")
      (node (ref "D12") (pin "1") (pinfunction "A_1") (pintype "passive"))
      (node (ref "R13") (pin "1") (pinfunction "1_1") (pintype "passive"))
    )
    (net (code "70") (name "Net-(D13-A)") (class "Default")
      (node (ref "D13") (pin "1") (pinfunction "A_1") (pintype "passive"))
      (node (ref "R14") (pin "1") (pinfunction "1_1") (pintype "passive"))
    )
    (net (code "71") (name "Net-(D14-A)") (class "Default")
      (node (ref "D14") (pin "1") (pinfunction "A_1") (pintype "passive"))
      (node (ref "R16") (pin "1") (pinfunction "1_1") (pintype "passive"))
    )
    (net (code "72") (name "Net-(D16-K)") (class "Default")
      (node (ref "D16") (pin "2") (pinfunction "K_2") (pintype "passive"))
      (node (ref "L2") (pin "1") (pinfunction "1_1") (pintype "passive"))
      (node (ref "U2") (pin "2") (pinfunction "OUT_2") (pintype "power_in"))
    )
    (net (code "73") (name "Net-(D17-A)") (class "Default")
      (node (ref "D17") (pin "1") (pinfunction "A_1") (pintype "passive"))
      (node (ref "P5") (pin "1") (pinfunction "1_1") (pintype "passive"))
    )
    (net (code "74") (name "Net-(D18-A)") (class "Default")
      (node (ref "D18") (pin "1") (pinfunction "A_1") (pintype "passive"))
      (node (ref "R12") (pin "1") (pinfunction "1_1") (pintype "passive"))
    )
    (net (code "75") (name "Net-(U1-AREF)") (class "Default")
      (node (ref "C6") (pin "2") (pinfunction "2_2") (pintype "passive"))
      (node (ref "U1") (pin "62") (pinfunction "AREF_62") (pintype "power_in"))
    )
    (net (code "76") (name "Net-(U1-AVCC)") (class "Default")
      (node (ref "C5") (pin "2") (pinfunction "2_2") (pintype "passive"))
      (node (ref "L1") (pin "1") (pinfunction "1_1") (pintype "passive"))
      (node (ref "U1") (pin "64") (pinfunction "AVCC_64") (pintype "power_in"))
    )
    (net (code "77") (name "Net-(U1-XTAL1)") (class "Default")
      (node (ref "C3") (pin "2") (pinfunction "2_2") (pintype "passive"))
      (node (ref "R15") (pin "1") (pinfunction "1_1") (pintype "passive"))
      (node (ref "U1") (pin "24") (pinfunction "XTAL1_24") (pintype "input"))
      (node (ref "Y1") (pin "1") (pinfunction "OSC1_1") (pintype "passive"))
    )
    (net (code "78") (name "Net-(U1-XTAL2)") (class "Default")
      (node (ref "C4") (pin "2") (pinfunction "2_2") (pintype "passive"))
      (node (ref "R15") (pin "2") (pinfunction "2_2") (pintype "passive"))
      (node (ref "U1") (pin "23") (pinfunction "XTAL2_23") (pintype "output"))
      (node (ref "Y1") (pin "2") (pinfunction "OSC2_2") (pintype "passive"))
    )
    (net (code "79") (name "VIN") (class "Default")
      (node (ref "C7") (pin "1") (pinfunction "1_1") (pintype "passive"))
      (node (ref "D17") (pin "2") (pinfunction "K_2") (pintype "passive"))
      (node (ref "U2") (pin "1") (pinfunction "VIN_1") (pintype "power_in"))
    )
    (net (code "80") (name "unconnected-(P1-Pad3)") (class "Default")
      (node (ref "P1") (pin "3") (pinfunction "3_3") (pintype "passive+no_connect"))
    )
    (net (code "81") (name "unconnected-(U1-~{PEN}-Pad1)") (class "Default")
      (node (ref "U1") (pin "1") (pinfunction "~{PEN}_1") (pintype "input"))
    )
  )
)
